# Arduino_Converter3_3V.net
KiCad netlist of a schematic drawn in Altium Designer
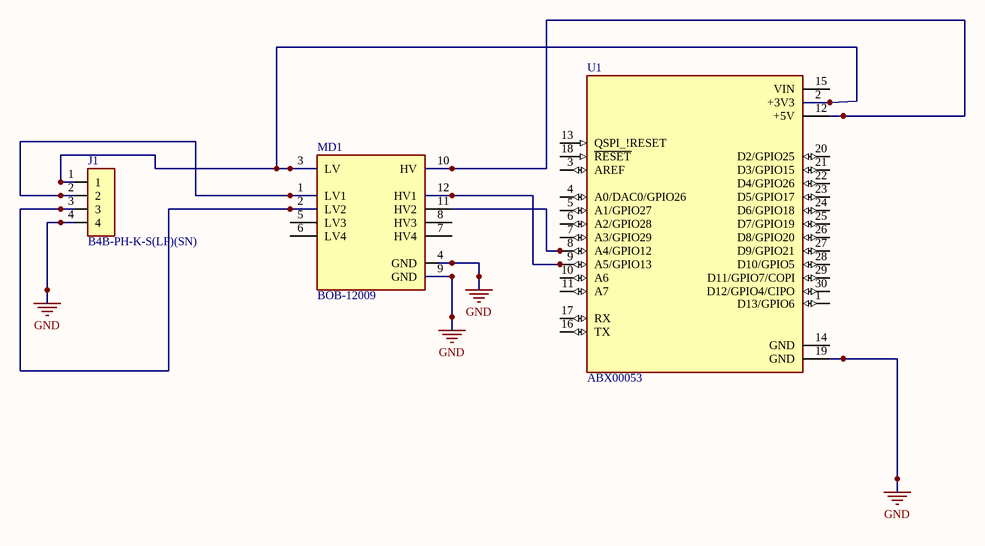
[diagram p0: Arduino_Converter3.3V.SchDoc]

(export (version "E")
  (design (tool "Eeschema 10.0.6"))
  (components
    (comp (ref "J1")
      (value "B4B-PH-K-S(LF)(SN)")
      (footprint "JST_B4B-PH-K-S(LF)(SN)")
      (description "PH Series 4 Position 2 mm Pitch Through Hole Crimp Top Entry Shrouded Header")
      (libsource (lib "B4B-PH-K-S_LF__SN_") (part "B4B-PH-K-S(LF)(SN)"))
    )
    (comp (ref "MD1")
      (value "BOB-12009")
      (footprint "FP-BOB-12009-MFG")
      (description "LOGIC LEVEL CONVERTER - BI-DIREC")
      (libsource (lib "sparkfun_logicconverter") (part "CMP-157458-000001-1"))
    )
    (comp (ref "U1")
      (value "ABX00053")
      (footprint "MODULE_ABX00053")
      (description "ARDUINO NANO RP2040 CONNECT WITH")
      (fields (field (name "MF") "Arduino"))
      (libsource (lib "ABX00053") (part "ABX00053"))
    )
  )
  (nets
    (net (code "1") (name "GND") (class "Default")
      (node (ref "J1") (pin "4") (pinfunction "4_4") (pintype "passive"))
      (node (ref "MD1") (pin "4") (pinfunction "GND_4") (pintype "power_in"))
      (node (ref "MD1") (pin "9") (pinfunction "GND_9") (pintype "power_in"))
      (node (ref "U1") (pin "19") (pinfunction "GND_19") (pintype "power_in"))
    )
    (net (code "2") (name "Net-(MD1-HV)") (class "Default")
      (node (ref "MD1") (pin "10") (pinfunction "HV_10") (pintype "passive"))
      (node (ref "U1") (pin "12") (pinfunction "+5V_12") (pintype "power_in"))
    )
    (net (code "3") (name "Net-(MD1-HV1)") (class "Default")
      (node (ref "MD1") (pin "12") (pinfunction "HV1_12") (pintype "passive"))
      (node (ref "U1") (pin "9") (pinfunction "A5/GPIO13_9") (pintype "bidirectional"))
    )
    (net (code "4") (name "Net-(MD1-HV2)") (class "Default")
      (node (ref "MD1") (pin "11") (pinfunction "HV2_11") (pintype "passive"))
      (node (ref "U1") (pin "8") (pinfunction "A4/GPIO12_8") (pintype "bidirectional"))
    )
    (net (code "5") (name "Net-(MD1-LV)") (class "Default")
      (node (ref "J1") (pin "1") (pinfunction "1_1") (pintype "passive"))
      (node (ref "MD1") (pin "3") (pinfunction "LV_3") (pintype "passive"))
      (node (ref "U1") (pin "2") (pinfunction "+3V3_2") (pintype "power_in"))
    )
    (net (code "6") (name "Net-(MD1-LV1)") (class "Default")
      (node (ref "J1") (pin "2") (pinfunction "2_2") (pintype "passive"))
      (node (ref "MD1") (pin "1") (pinfunction "LV1_1") (pintype "passive"))
    )
    (net (code "7") (name "Net-(MD1-LV2)") (class "Default")
      (node (ref "J1") (pin "3") (pinfunction "3_3") (pintype "passive"))
      (node (ref "MD1") (pin "2") (pinfunction "LV2_2") (pintype "passive"))
    )
    (net (code "8") (name "unconnected-(MD1-HV3-Pad8)") (class "Default")
      (node (ref "MD1") (pin "8") (pinfunction "HV3_8") (pintype "passive"))
    )
    (net (code "9") (name "unconnected-(MD1-HV4-Pad7)") (class "Default")
      (node (ref "MD1") (pin "7") (pinfunction "HV4_7") (pintype "passive"))
    )
    (net (code "10") (name "unconnected-(MD1-LV3-Pad5)") (class "Default")
      (node (ref "MD1") (pin "5") (pinfunction "LV3_5") (pintype "passive"))
    )
    (net (code "11") (name "unconnected-(MD1-LV4-Pad6)") (class "Default")
      (node (ref "MD1") (pin "6") (pinfunction "LV4_6") (pintype "passive"))
    )
    (net (code "12") (name "unconnected-(U1-A0{slash}DAC0{slash}GPIO26-Pad4)") (class "Default")
      (node (ref "U1") (pin "4") (pinfunction "A0/DAC0/GPIO26_4") (pintype "bidirectional"))
    )
    (net (code "13") (name "unconnected-(U1-A1{slash}GPIO27-Pad5)") (class "Default")
      (node (ref "U1") (pin "5") (pinfunction "A1/GPIO27_5") (pintype "bidirectional"))
    )
    (net (code "14") (name "unconnected-(U1-A2{slash}GPIO28-Pad6)") (class "Default")
      (node (ref "U1") (pin "6") (pinfunction "A2/GPIO28_6") (pintype "bidirectional"))
    )
    (net (code "15") (name "unconnected-(U1-A3{slash}GPIO29-Pad7)") (class "Default")
      (node (ref "U1") (pin "7") (pinfunction "A3/GPIO29_7") (pintype "bidirectional"))
    )
    (net (code "16") (name "unconnected-(U1-A6-Pad10)") (class "Default")
      (node (ref "U1") (pin "10") (pinfunction "A6_10") (pintype "bidirectional"))
    )
    (net (code "17") (name "unconnected-(U1-A7-Pad11)") (class "Default")
      (node (ref "U1") (pin "11") (pinfunction "A7_11") (pintype "bidirectional"))
    )
    (net (code "18") (name "unconnected-(U1-AREF-Pad3)") (class "Default")
      (node (ref "U1") (pin "3") (pinfunction "AREF_3") (pintype "bidirectional"))
    )
    (net (code "19") (name "unconnected-(U1-D2{slash}GPIO25-Pad20)") (class "Default")
      (node (ref "U1") (pin "20") (pinfunction "D2/GPIO25_20") (pintype "bidirectional"))
    )
    (net (code "20") (name "unconnected-(U1-D3{slash}GPIO15-Pad21)") (class "Default")
      (node (ref "U1") (pin "21") (pinfunction "D3/GPIO15_21") (pintype "bidirectional"))
    )
    (net (code "21") (name "unconnected-(U1-D4{slash}GPIO26-Pad22)") (class "Default")
      (node (ref "U1") (pin "22") (pinfunction "D4/GPIO26_22") (pintype "bidirectional"))
    )
    (net (code "22") (name "unconnected-(U1-D5{slash}GPIO17-Pad23)") (class "Default")
      (node (ref "U1") (pin "23") (pinfunction "D5/GPIO17_23") (pintype "bidirectional"))
    )
    (net (code "23") (name "unconnected-(U1-D6{slash}GPIO18-Pad24)") (class "Default")
      (node (ref "U1") (pin "24") (pinfunction "D6/GPIO18_24") (pintype "bidirectional"))
    )
    (net (code "24") (name "unconnected-(U1-D7{slash}GPIO19-Pad25)") (class "Default")
      (node (ref "U1") (pin "25") (pinfunction "D7/GPIO19_25") (pintype "bidirectional"))
    )
    (net (code "25") (name "unconnected-(U1-D8{slash}GPIO20-Pad26)") (class "Default")
      (node (ref "U1") (pin "26") (pinfunction "D8/GPIO20_26") (pintype "bidirectional"))
    )
    (net (code "26") (name "unconnected-(U1-D9{slash}GPIO21-Pad27)") (class "Default")
      (node (ref "U1") (pin "27") (pinfunction "D9/GPIO21_27") (pintype "bidirectional"))
    )
    (net (code "27") (name "unconnected-(U1-D10{slash}GPIO5-Pad28)") (class "Default")
      (node (ref "U1") (pin "28") (pinfunction "D10/GPIO5_28") (pintype "bidirectional"))
    )
    (net (code "28") (name "unconnected-(U1-D11{slash}GPIO7{slash}COPI-Pad29)") (class "Default")
      (node (ref "U1") (pin "29") (pinfunction "D11/GPIO7/COPI_29") (pintype "bidirectional"))
    )
    (net (code "29") (name "unconnected-(U1-D12{slash}GPIO4{slash}CIPO-Pad30)") (class "Default")
      (node (ref "U1") (pin "30") (pinfunction "D12/GPIO4/CIPO_30") (pintype "bidirectional"))
    )
    (net (code "30") (name "unconnected-(U1-D13{slash}GPIO6-Pad1)") (class "Default")
      (node (ref "U1") (pin "1") (pinfunction "D13/GPIO6_1") (pintype "bidirectional"))
    )
    (net (code "31") (name "unconnected-(U1-GND-Pad14)") (class "Default")
      (node (ref "U1") (pin "14") (pinfunction "GND_14") (pintype "power_in"))
    )
    (net (code "32") (name "unconnected-(U1-QSPI_!RESET-Pad13)") (class "Default")
      (node (ref "U1") (pin "13") (pinfunction "QSPI_!RESET_13") (pintype "input"))
    )
    (net (code "33") (name "unconnected-(U1-RX-Pad17)") (class "Default")
      (node (ref "U1") (pin "17") (pinfunction "RX_17") (pintype "bidirectional"))
    )
    (net (code "34") (name "unconnected-(U1-TX-Pad16)") (class "Default")
      (node (ref "U1") (pin "16") (pinfunction "TX_16") (pintype "bidirectional"))
    )
    (net (code "35") (name "unconnected-(U1-VIN-Pad15)") (class "Default")
      (node (ref "U1") (pin "15") (pinfunction "VIN_15") (pintype "power_in"))
    )
    (net (code "36") (name "unconnected-(U1-~{RESET}-Pad18)") (class "Default")
      (node (ref "U1") (pin "18") (pinfunction "~{RESET}_18") (pintype "input"))
    )
  )
)
